# FT232_USB_to_TTL_Converter.net
KiCad netlist of a schematic drawn in EAGLE
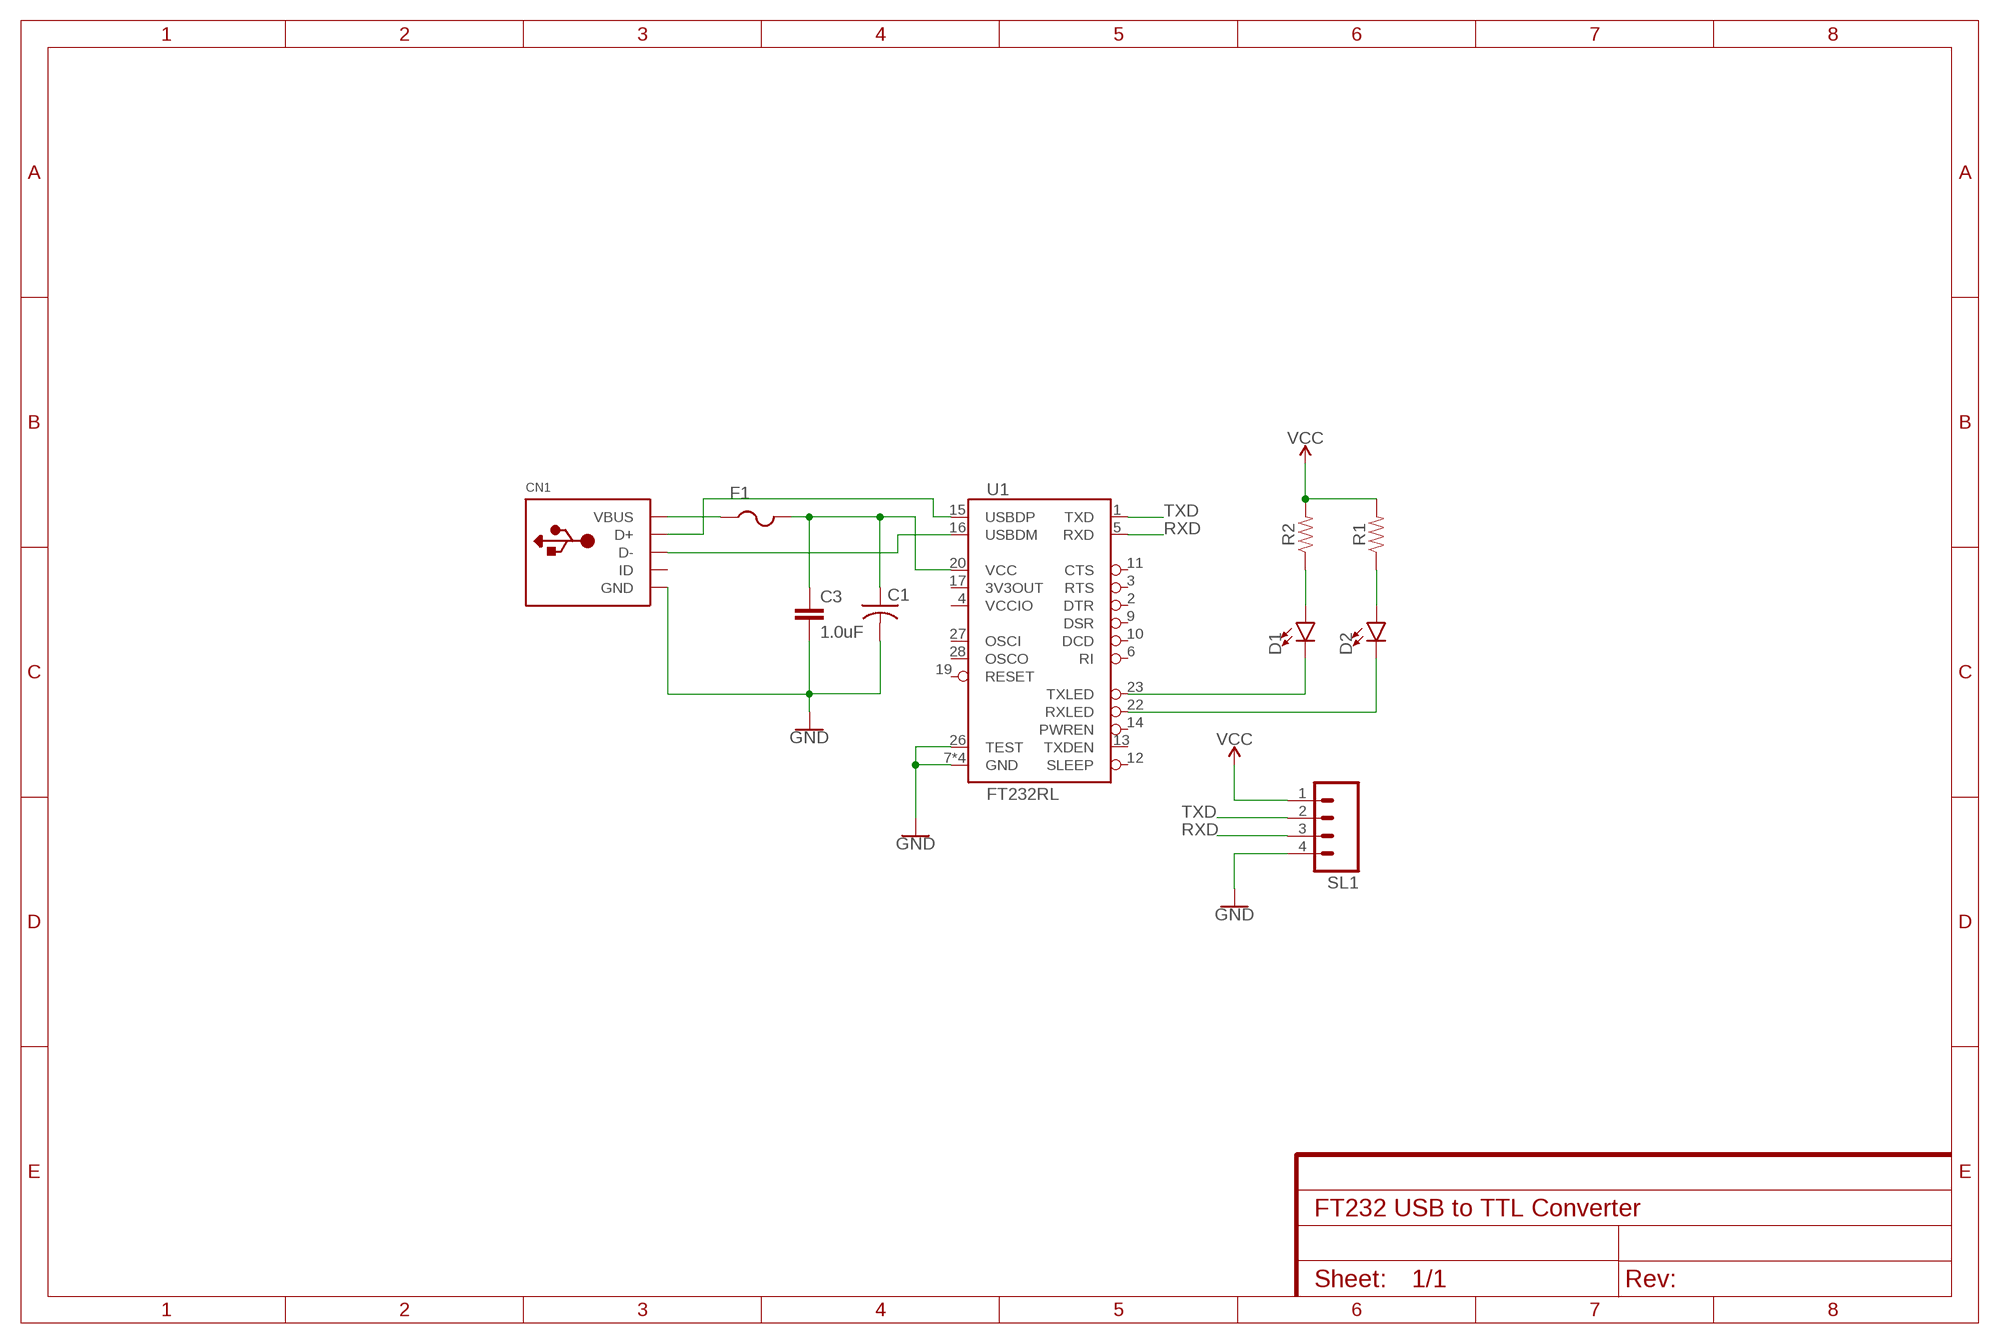
[diagram p0: schematic, sheet 1]

(export (version "E")
  (design (tool "Eeschema 10.0.6"))
  (components
    (comp (ref "C1")
      (value "C-USC1206")
      (footprint "eagle-import:C1206")
      (libsource (lib "eagle-import") (part "C-USC1206"))
    )
    (comp (ref "C3")
      (value "1.0uF")
      (footprint "eagle-import:1206")
      (libsource (lib "eagle-import") (part "1.0UF-1206-50V-10%"))
    )
    (comp (ref "CN1")
      (value "USBMOLEX")
      (footprint "eagle-import:USB-MINIB-THM-MOLEX")
      (libsource (lib "eagle-import") (part "USBMOLEX"))
    )
    (comp (ref "D1")
      (value "LED1206")
      (footprint "eagle-import:LED-1206")
      (libsource (lib "eagle-import") (part "LED1206"))
    )
    (comp (ref "D2")
      (value "LED1206")
      (footprint "eagle-import:LED-1206")
      (libsource (lib "eagle-import") (part "LED1206"))
    )
    (comp (ref "F1")
      (value "PTCFUSE-1206")
      (footprint "eagle-import:R1206")
      (libsource (lib "eagle-import") (part "PTCFUSE-1206"))
    )
    (comp (ref "R1")
      (value "RESISTOR1206")
      (footprint "eagle-import:1206")
      (libsource (lib "eagle-import") (part "RESISTOR1206"))
    )
    (comp (ref "R2")
      (value "RESISTOR1206")
      (footprint "eagle-import:1206")
      (libsource (lib "eagle-import") (part "RESISTOR1206"))
    )
    (comp (ref "SL1")
      (value "M04")
      (footprint "eagle-import:04P")
      (libsource (lib "eagle-import") (part "M04"))
    )
    (comp (ref "U1")
      (value "FT232RL")
      (footprint "eagle-import:SSOP28DB")
      (libsource (lib "eagle-import") (part "FT232RLSSOP"))
    )
  )
  (nets
    (net (code "1") (name "/RXD") (class "Default")
      (node (ref "SL1") (pin "3") (pinfunction "3_3") (pintype "passive"))
      (node (ref "U1") (pin "5") (pinfunction "RXD_5") (pintype "input"))
    )
    (net (code "2") (name "/TXD") (class "Default")
      (node (ref "SL1") (pin "2") (pinfunction "2_2") (pintype "passive"))
      (node (ref "U1") (pin "1") (pinfunction "TXD_1") (pintype "output"))
    )
    (net (code "3") (name "/VCCIO") (class "Default")
      (node (ref "U1") (pin "4") (pinfunction "VCCIO_4") (pintype "power_in"))
    )
    (net (code "4") (name "GND") (class "Default")
      (node (ref "C1") (pin "2") (pinfunction "2_2") (pintype "passive"))
      (node (ref "C3") (pin "2") (pinfunction "2_2") (pintype "passive"))
      (node (ref "CN1") (pin "GND") (pinfunction "GND_GND") (pintype "power_in"))
      (node (ref "SL1") (pin "4") (pinfunction "4_4") (pintype "passive"))
      (node (ref "U1") (pin "18") (pinfunction "GND_18") (pintype "power_in"))
      (node (ref "U1") (pin "21") (pinfunction "GND_21") (pintype "power_in"))
      (node (ref "U1") (pin "25") (pinfunction "GND_25") (pintype "power_in"))
      (node (ref "U1") (pin "26") (pinfunction "TEST_26") (pintype "input"))
      (node (ref "U1") (pin "7") (pinfunction "GND_7") (pintype "power_in"))
    )
    (net (code "5") (name "Net-(CN1-PadVBUS)") (class "Default")
      (node (ref "CN1") (pin "VBUS") (pinfunction "VBUS_VBUS") (pintype "power_in"))
      (node (ref "F1") (pin "1") (pinfunction "1_1") (pintype "passive"))
    )
    (net (code "6") (name "Net-(D1-PadA)") (class "Default")
      (node (ref "D1") (pin "A") (pinfunction "A_A") (pintype "passive"))
      (node (ref "R2") (pin "1") (pinfunction "1_1") (pintype "passive"))
    )
    (net (code "7") (name "Net-(D2-PadA)") (class "Default")
      (node (ref "D2") (pin "A") (pinfunction "A_A") (pintype "passive"))
      (node (ref "R1") (pin "1") (pinfunction "1_1") (pintype "passive"))
    )
    (net (code "8") (name "Net-(U1-RXLED)") (class "Default")
      (node (ref "D2") (pin "C") (pinfunction "C_C") (pintype "passive"))
      (node (ref "U1") (pin "22") (pinfunction "RXLED_22") (pintype "input"))
    )
    (net (code "9") (name "Net-(U1-TXLED)") (class "Default")
      (node (ref "D1") (pin "C") (pinfunction "C_C") (pintype "passive"))
      (node (ref "U1") (pin "23") (pinfunction "TXLED_23") (pintype "input"))
    )
    (net (code "10") (name "Net-(U1-USBDM)") (class "Default")
      (node (ref "CN1") (pin "D-") (pinfunction "D-_D-") (pintype "bidirectional"))
      (node (ref "U1") (pin "16") (pinfunction "USBDM_16") (pintype "bidirectional"))
    )
    (net (code "11") (name "Net-(U1-USBDP)") (class "Default")
      (node (ref "CN1") (pin "D+") (pinfunction "D+_D+") (pintype "bidirectional"))
      (node (ref "U1") (pin "15") (pinfunction "USBDP_15") (pintype "bidirectional"))
    )
    (net (code "12") (name "Net-(U1-VCC)") (class "Default")
      (node (ref "C1") (pin "1") (pinfunction "1_1") (pintype "passive"))
      (node (ref "C3") (pin "1") (pinfunction "1_1") (pintype "passive"))
      (node (ref "F1") (pin "2") (pinfunction "2_2") (pintype "passive"))
      (node (ref "U1") (pin "20") (pinfunction "VCC_20") (pintype "power_in"))
    )
    (net (code "13") (name "VCC") (class "Default")
      (node (ref "R1") (pin "2") (pinfunction "2_2") (pintype "passive"))
      (node (ref "R2") (pin "2") (pinfunction "2_2") (pintype "passive"))
      (node (ref "SL1") (pin "1") (pinfunction "1_1") (pintype "passive"))
    )
    (net (code "14") (name "unconnected-(CN1-PadID)") (class "Default")
      (node (ref "CN1") (pin "ID") (pinfunction "ID_ID") (pintype "bidirectional"))
    )
    (net (code "15") (name "unconnected-(U1-3V3OUT-Pad17)") (class "Default")
      (node (ref "U1") (pin "17") (pinfunction "3V3OUT_17") (pintype "output"))
    )
    (net (code "16") (name "unconnected-(U1-CTS-Pad11)") (class "Default")
      (node (ref "U1") (pin "11") (pinfunction "CTS_11") (pintype "input"))
    )
    (net (code "17") (name "unconnected-(U1-DCD-Pad10)") (class "Default")
      (node (ref "U1") (pin "10") (pinfunction "DCD_10") (pintype "input"))
    )
    (net (code "18") (name "unconnected-(U1-DSR-Pad9)") (class "Default")
      (node (ref "U1") (pin "9") (pinfunction "DSR_9") (pintype "input"))
    )
    (net (code "19") (name "unconnected-(U1-DTR-Pad2)") (class "Default")
      (node (ref "U1") (pin "2") (pinfunction "DTR_2") (pintype "output"))
    )
    (net (code "20") (name "unconnected-(U1-OSCI-Pad27)") (class "Default")
      (node (ref "U1") (pin "27") (pinfunction "OSCI_27") (pintype "input"))
    )
    (net (code "21") (name "unconnected-(U1-OSCO-Pad28)") (class "Default")
      (node (ref "U1") (pin "28") (pinfunction "OSCO_28") (pintype "output"))
    )
    (net (code "22") (name "unconnected-(U1-PWREN-Pad14)") (class "Default")
      (node (ref "U1") (pin "14") (pinfunction "PWREN_14") (pintype "input"))
    )
    (net (code "23") (name "unconnected-(U1-RESET-Pad19)") (class "Default")
      (node (ref "U1") (pin "19") (pinfunction "RESET_19") (pintype "input"))
    )
    (net (code "24") (name "unconnected-(U1-RI-Pad6)") (class "Default")
      (node (ref "U1") (pin "6") (pinfunction "RI_6") (pintype "input"))
    )
    (net (code "25") (name "unconnected-(U1-RTS-Pad3)") (class "Default")
      (node (ref "U1") (pin "3") (pinfunction "RTS_3") (pintype "output"))
    )
    (net (code "26") (name "unconnected-(U1-SLEEP-Pad12)") (class "Default")
      (node (ref "U1") (pin "12") (pinfunction "SLEEP_12") (pintype "input"))
    )
    (net (code "27") (name "unconnected-(U1-TXDEN-Pad13)") (class "Default")
      (node (ref "U1") (pin "13") (pinfunction "TXDEN_13") (pintype "input"))
    )
  )
)
